# 23_Unused.net
KiCad netlist of a schematic drawn in Altium Designer
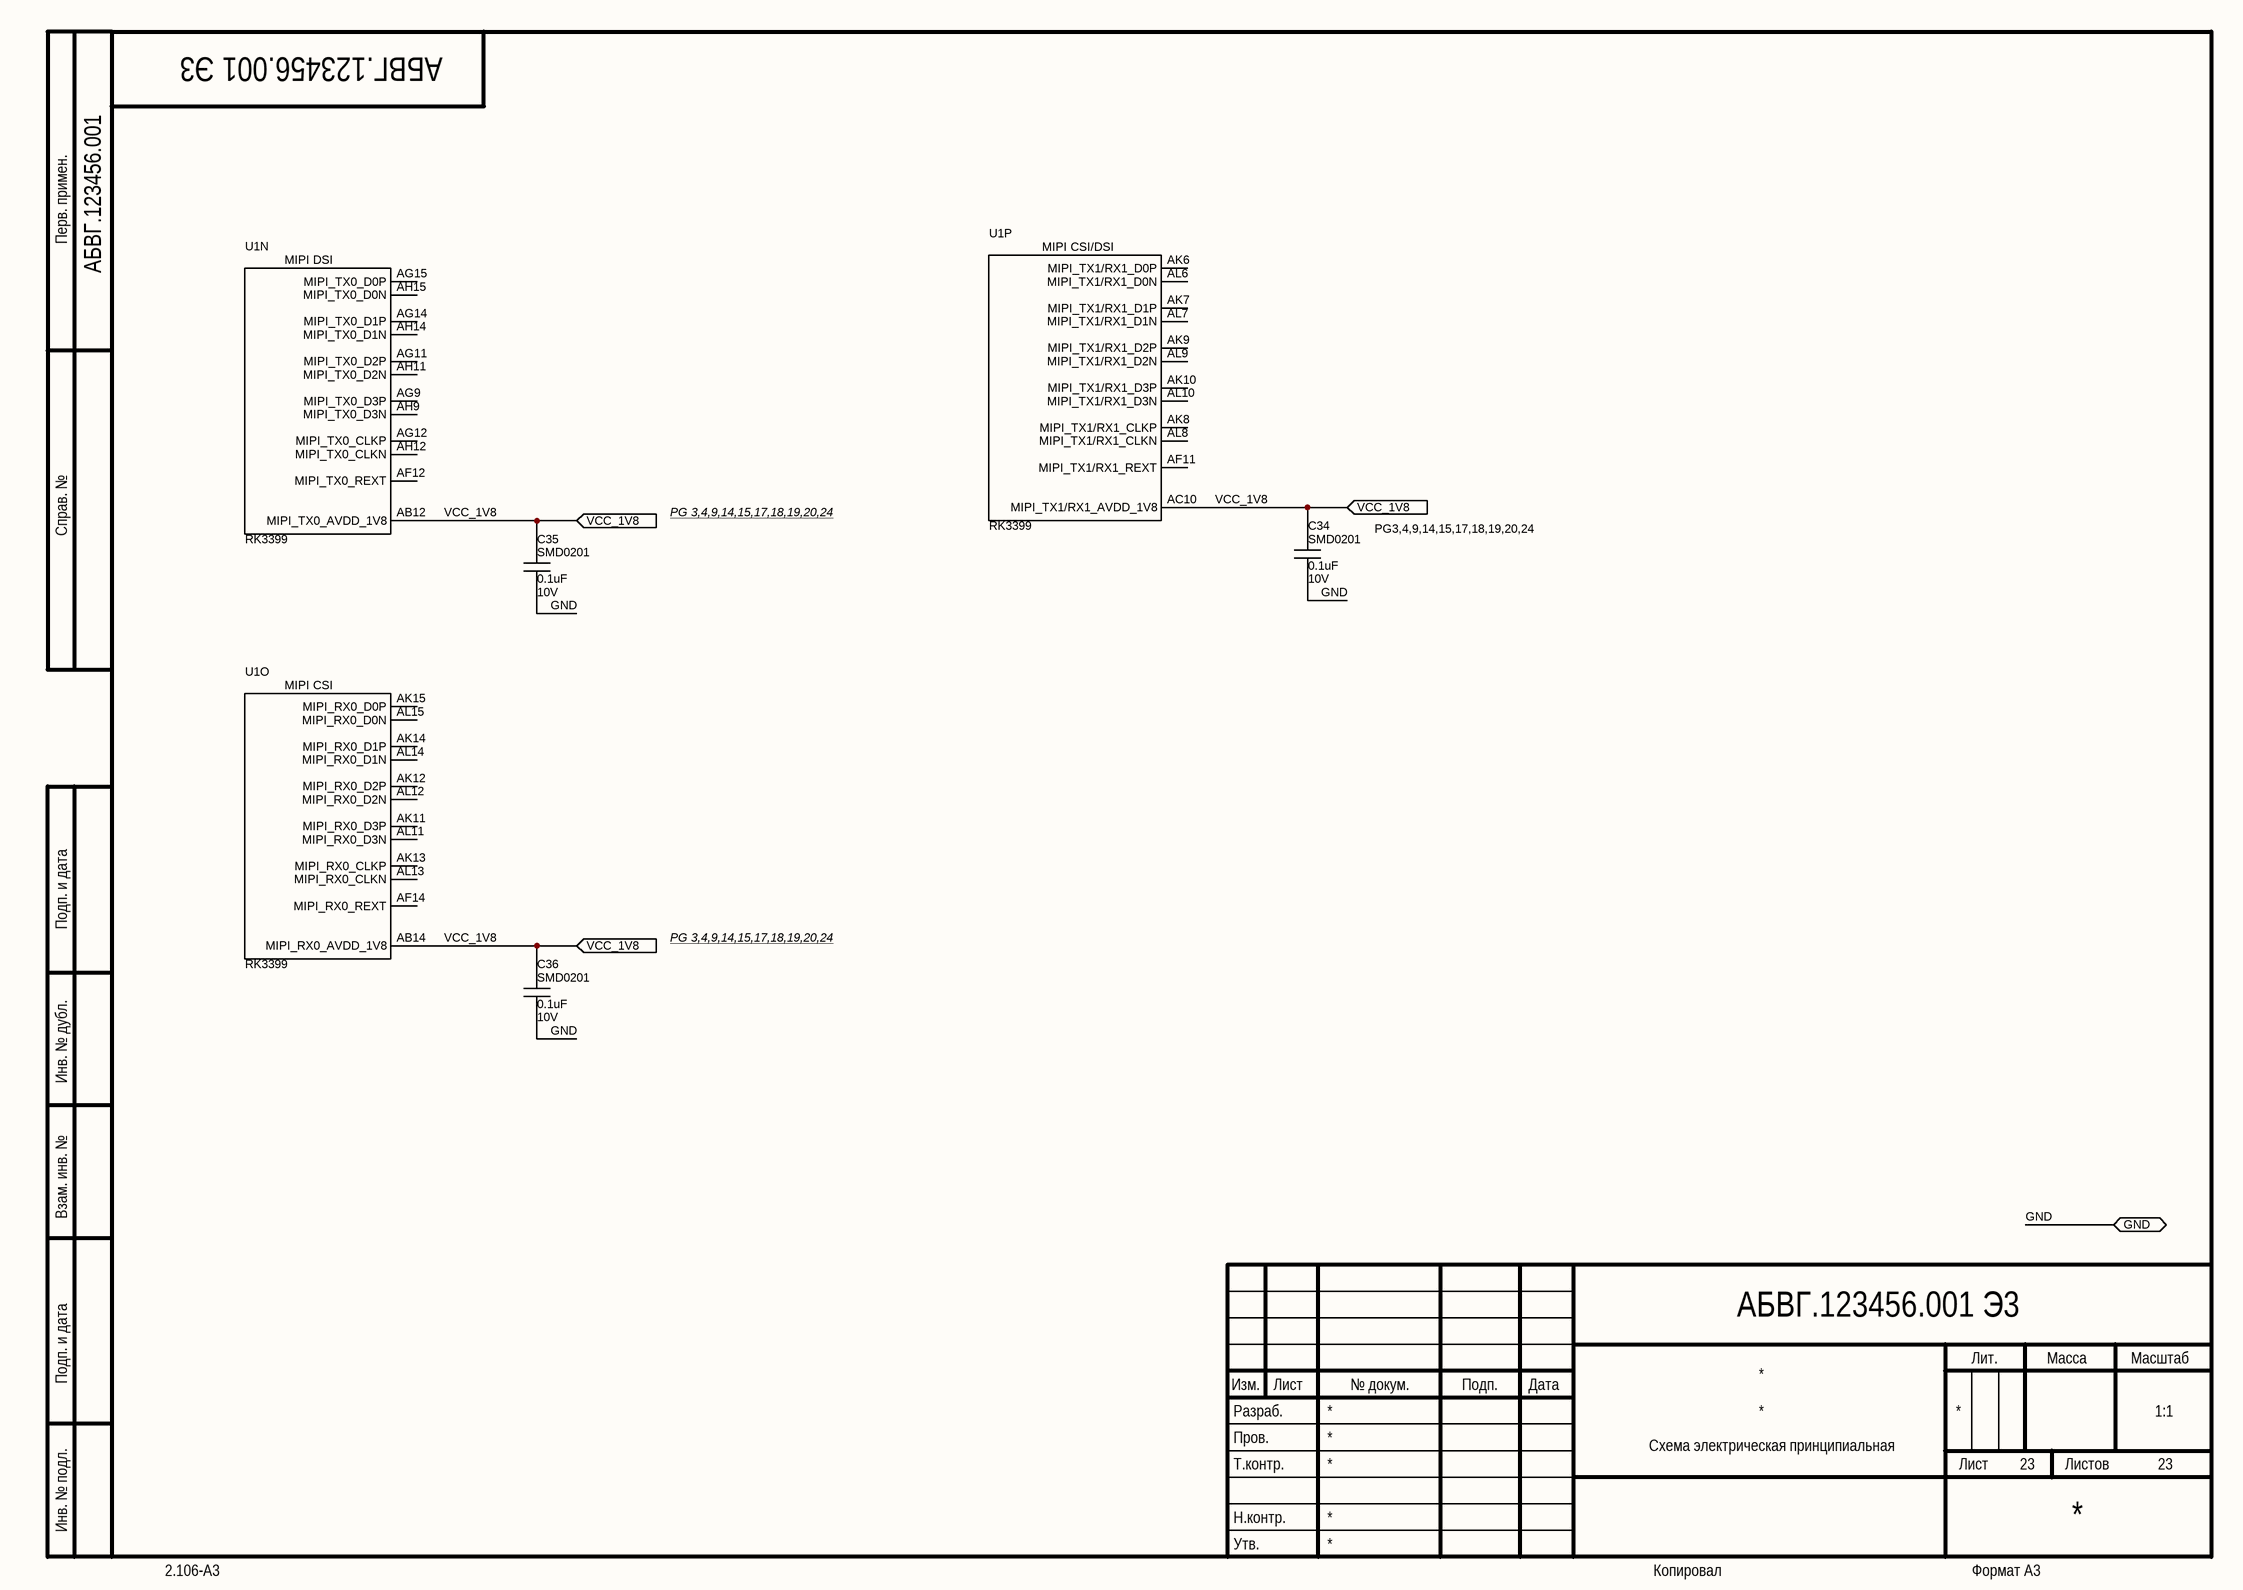
[diagram p0: 23 Unused.SchDoc]

(export (version "E")
  (design (tool "Eeschema 10.0.6"))
  (components
    (comp (ref "C34")
      (value "0.1uF")
      (footprint "Didur_PcbLib_1:CAP_SMD_0201")
      (fields
        (field (name "PACKAGE") "SMD0201")
        (field (name "PARTNUMBER") "CC0201KRX5R6BB104")
        (field (name "VOLTAGE") "10V")
      )
      (libsource (lib "Didur_SchLib_1") (part "Ceramic_Cap"))
    )
    (comp (ref "C35")
      (value "0.1uF")
      (footprint "Didur_PcbLib_1:CAP_SMD_0201")
      (fields
        (field (name "PACKAGE") "SMD0201")
        (field (name "PARTNUMBER") "CC0201KRX5R6BB104")
        (field (name "VOLTAGE") "10V")
      )
      (libsource (lib "Didur_SchLib_1") (part "Ceramic_Cap"))
    )
    (comp (ref "C36")
      (value "0.1uF")
      (footprint "Didur_PcbLib_1:CAP_SMD_0201")
      (fields
        (field (name "PACKAGE") "SMD0201")
        (field (name "PARTNUMBER") "CC0201KRX5R6BB104")
        (field (name "VOLTAGE") "10V")
      )
      (libsource (lib "Didur_SchLib_1") (part "Ceramic_Cap"))
    )
    (comp (ref "U1")
      (value "RK3399")
      (footprint "BGA828C65P31X31_2100X2100X161N")
      (fields (field (name "Comment") "RK3399_FF"))
      (libsource (lib "Didur_SchLib_1") (part "RK3399_FF"))
    )
  )
  (nets
    (net (code "1") (name "/GND") (class "Default")
      (node (ref "C34") (pin "2") (pinfunction "2_2") (pintype "power_in"))
      (node (ref "C35") (pin "2") (pinfunction "2_2") (pintype "power_in"))
      (node (ref "C36") (pin "2") (pinfunction "2_2") (pintype "power_in"))
    )
    (net (code "2") (name "/VCC_1V8") (class "Default")
      (node (ref "C34") (pin "1") (pinfunction "1_1") (pintype "power_in"))
      (node (ref "C35") (pin "1") (pinfunction "1_1") (pintype "power_in"))
      (node (ref "C36") (pin "1") (pinfunction "1_1") (pintype "power_in"))
      (node (ref "U1") (pin "AB12") (pinfunction "MIPI_TX0_AVDD_1V8_AB12") (pintype "passive"))
      (node (ref "U1") (pin "AB14") (pinfunction "MIPI_RX0_AVDD_1V8_AB14") (pintype "passive"))
      (node (ref "U1") (pin "AC10") (pinfunction "MIPI_TX1/RX1_AVDD_1V8_AC10") (pintype "passive"))
    )
    (net (code "3") (name "unconnected-(U1N-MIPI_TX0_CLKN-PadAH12)") (class "Default")
      (node (ref "U1") (pin "AH12") (pinfunction "MIPI_TX0_CLKN_AH12") (pintype "passive"))
    )
    (net (code "4") (name "unconnected-(U1N-MIPI_TX0_CLKP-PadAG12)") (class "Default")
      (node (ref "U1") (pin "AG12") (pinfunction "MIPI_TX0_CLKP_AG12") (pintype "passive"))
    )
    (net (code "5") (name "unconnected-(U1N-MIPI_TX0_D0N-PadAH15)") (class "Default")
      (node (ref "U1") (pin "AH15") (pinfunction "MIPI_TX0_D0N_AH15") (pintype "passive"))
    )
    (net (code "6") (name "unconnected-(U1N-MIPI_TX0_D0P-PadAG15)") (class "Default")
      (node (ref "U1") (pin "AG15") (pinfunction "MIPI_TX0_D0P_AG15") (pintype "passive"))
    )
    (net (code "7") (name "unconnected-(U1N-MIPI_TX0_D1N-PadAH14)") (class "Default")
      (node (ref "U1") (pin "AH14") (pinfunction "MIPI_TX0_D1N_AH14") (pintype "passive"))
    )
    (net (code "8") (name "unconnected-(U1N-MIPI_TX0_D1P-PadAG14)") (class "Default")
      (node (ref "U1") (pin "AG14") (pinfunction "MIPI_TX0_D1P_AG14") (pintype "passive"))
    )
    (net (code "9") (name "unconnected-(U1N-MIPI_TX0_D2N-PadAH11)") (class "Default")
      (node (ref "U1") (pin "AH11") (pinfunction "MIPI_TX0_D2N_AH11") (pintype "passive"))
    )
    (net (code "10") (name "unconnected-(U1N-MIPI_TX0_D2P-PadAG11)") (class "Default")
      (node (ref "U1") (pin "AG11") (pinfunction "MIPI_TX0_D2P_AG11") (pintype "passive"))
    )
    (net (code "11") (name "unconnected-(U1N-MIPI_TX0_D3N-PadAH9)") (class "Default")
      (node (ref "U1") (pin "AH9") (pinfunction "MIPI_TX0_D3N_AH9") (pintype "passive"))
    )
    (net (code "12") (name "unconnected-(U1N-MIPI_TX0_D3P-PadAG9)") (class "Default")
      (node (ref "U1") (pin "AG9") (pinfunction "MIPI_TX0_D3P_AG9") (pintype "passive"))
    )
    (net (code "13") (name "unconnected-(U1N-MIPI_TX0_REXT-PadAF12)") (class "Default")
      (node (ref "U1") (pin "AF12") (pinfunction "MIPI_TX0_REXT_AF12") (pintype "passive"))
    )
    (net (code "14") (name "unconnected-(U1O-MIPI_RX0_CLKN-PadAL13)") (class "Default")
      (node (ref "U1") (pin "AL13") (pinfunction "MIPI_RX0_CLKN_AL13") (pintype "passive"))
    )
    (net (code "15") (name "unconnected-(U1O-MIPI_RX0_CLKP-PadAK13)") (class "Default")
      (node (ref "U1") (pin "AK13") (pinfunction "MIPI_RX0_CLKP_AK13") (pintype "passive"))
    )
    (net (code "16") (name "unconnected-(U1O-MIPI_RX0_D0N-PadAL15)") (class "Default")
      (node (ref "U1") (pin "AL15") (pinfunction "MIPI_RX0_D0N_AL15") (pintype "passive"))
    )
    (net (code "17") (name "unconnected-(U1O-MIPI_RX0_D0P-PadAK15)") (class "Default")
      (node (ref "U1") (pin "AK15") (pinfunction "MIPI_RX0_D0P_AK15") (pintype "passive"))
    )
    (net (code "18") (name "unconnected-(U1O-MIPI_RX0_D1N-PadAL14)") (class "Default")
      (node (ref "U1") (pin "AL14") (pinfunction "MIPI_RX0_D1N_AL14") (pintype "passive"))
    )
    (net (code "19") (name "unconnected-(U1O-MIPI_RX0_D1P-PadAK14)") (class "Default")
      (node (ref "U1") (pin "AK14") (pinfunction "MIPI_RX0_D1P_AK14") (pintype "passive"))
    )
    (net (code "20") (name "unconnected-(U1O-MIPI_RX0_D2N-PadAL12)") (class "Default")
      (node (ref "U1") (pin "AL12") (pinfunction "MIPI_RX0_D2N_AL12") (pintype "passive"))
    )
    (net (code "21") (name "unconnected-(U1O-MIPI_RX0_D2P-PadAK12)") (class "Default")
      (node (ref "U1") (pin "AK12") (pinfunction "MIPI_RX0_D2P_AK12") (pintype "passive"))
    )
    (net (code "22") (name "unconnected-(U1O-MIPI_RX0_D3N-PadAL11)") (class "Default")
      (node (ref "U1") (pin "AL11") (pinfunction "MIPI_RX0_D3N_AL11") (pintype "passive"))
    )
    (net (code "23") (name "unconnected-(U1O-MIPI_RX0_D3P-PadAK11)") (class "Default")
      (node (ref "U1") (pin "AK11") (pinfunction "MIPI_RX0_D3P_AK11") (pintype "passive"))
    )
    (net (code "24") (name "unconnected-(U1O-MIPI_RX0_REXT-PadAF14)") (class "Default")
      (node (ref "U1") (pin "AF14") (pinfunction "MIPI_RX0_REXT_AF14") (pintype "passive"))
    )
    (net (code "25") (name "unconnected-(U1P-MIPI_TX1{slash}RX1_CLKN-PadAL8)") (class "Default")
      (node (ref "U1") (pin "AL8") (pinfunction "MIPI_TX1/RX1_CLKN_AL8") (pintype "passive"))
    )
    (net (code "26") (name "unconnected-(U1P-MIPI_TX1{slash}RX1_CLKP-PadAK8)") (class "Default")
      (node (ref "U1") (pin "AK8") (pinfunction "MIPI_TX1/RX1_CLKP_AK8") (pintype "passive"))
    )
    (net (code "27") (name "unconnected-(U1P-MIPI_TX1{slash}RX1_D0N-PadAL6)") (class "Default")
      (node (ref "U1") (pin "AL6") (pinfunction "MIPI_TX1/RX1_D0N_AL6") (pintype "passive"))
    )
    (net (code "28") (name "unconnected-(U1P-MIPI_TX1{slash}RX1_D0P-PadAK6)") (class "Default")
      (node (ref "U1") (pin "AK6") (pinfunction "MIPI_TX1/RX1_D0P_AK6") (pintype "passive"))
    )
    (net (code "29") (name "unconnected-(U1P-MIPI_TX1{slash}RX1_D1N-PadAL7)") (class "Default")
      (node (ref "U1") (pin "AL7") (pinfunction "MIPI_TX1/RX1_D1N_AL7") (pintype "passive"))
    )
    (net (code "30") (name "unconnected-(U1P-MIPI_TX1{slash}RX1_D1P-PadAK7)") (class "Default")
      (node (ref "U1") (pin "AK7") (pinfunction "MIPI_TX1/RX1_D1P_AK7") (pintype "passive"))
    )
    (net (code "31") (name "unconnected-(U1P-MIPI_TX1{slash}RX1_D2N-PadAL9)") (class "Default")
      (node (ref "U1") (pin "AL9") (pinfunction "MIPI_TX1/RX1_D2N_AL9") (pintype "passive"))
    )
    (net (code "32") (name "unconnected-(U1P-MIPI_TX1{slash}RX1_D2P-PadAK9)") (class "Default")
      (node (ref "U1") (pin "AK9") (pinfunction "MIPI_TX1/RX1_D2P_AK9") (pintype "passive"))
    )
    (net (code "33") (name "unconnected-(U1P-MIPI_TX1{slash}RX1_D3N-PadAL10)") (class "Default")
      (node (ref "U1") (pin "AL10") (pinfunction "MIPI_TX1/RX1_D3N_AL10") (pintype "passive"))
    )
    (net (code "34") (name "unconnected-(U1P-MIPI_TX1{slash}RX1_D3P-PadAK10)") (class "Default")
      (node (ref "U1") (pin "AK10") (pinfunction "MIPI_TX1/RX1_D3P_AK10") (pintype "passive"))
    )
    (net (code "35") (name "unconnected-(U1P-MIPI_TX1{slash}RX1_REXT-PadAF11)") (class "Default")
      (node (ref "U1") (pin "AF11") (pinfunction "MIPI_TX1/RX1_REXT_AF11") (pintype "passive"))
    )
  )
)
